# connectors.net
KiCad netlist of a schematic drawn in Altium Designer
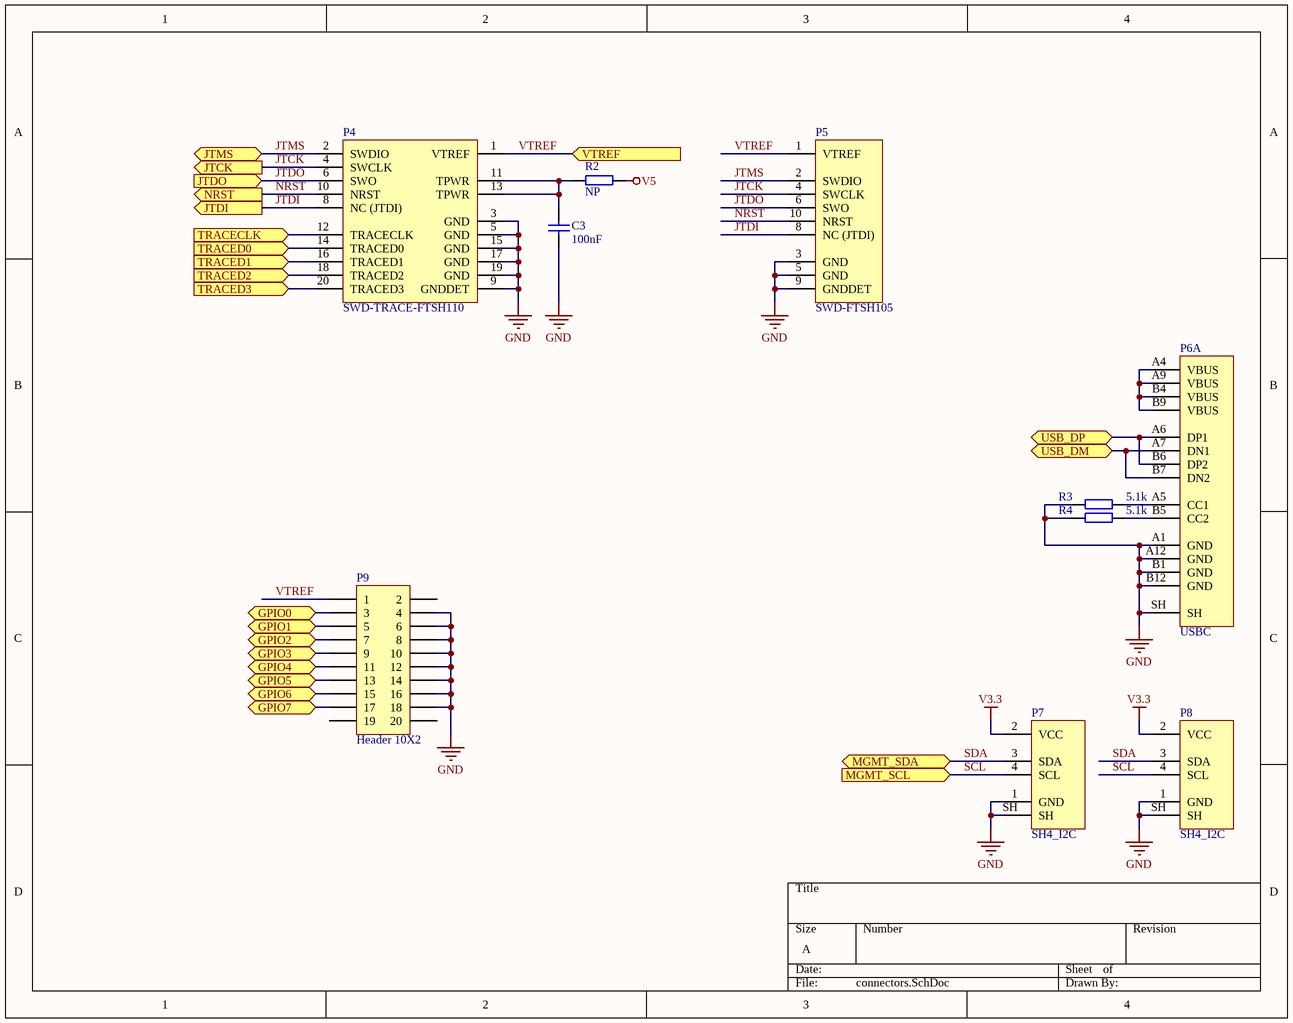
[diagram p0: connectors.SchDoc]

(export (version "E")
  (design (tool "Eeschema 10.0.6"))
  (components
    (comp (ref "C3") (value "100nF") (footprint "0402") (libsource (lib "misc") (part "Capacitor")))
    (comp (ref "P4")
      (value "SWD-TRACE-FTSH110")
      (footprint "FTSH110")
      (libsource (lib "misc") (part "SWD-TRACE-FTSH110"))
    )
    (comp (ref "P5")
      (value "SWD-FTSH105")
      (footprint "FTSH105")
      (libsource (lib "misc") (part "SWD-FTSH105"))
    )
    (comp (ref "P6") (value "USBC") (footprint "U262-161N-4BVC11") (libsource (lib "misc") (part "USBC")))
    (comp (ref "P7")
      (value "SH4_I2C")
      (footprint "SM04B")
      (description "Qwiic / STEMMA QT Compatible")
      (libsource (lib "misc") (part "SH4_I2C"))
    )
    (comp (ref "P8")
      (value "SH4_I2C")
      (footprint "SM04B")
      (description "Qwiic / STEMMA QT Compatible")
      (libsource (lib "misc") (part "SH4_I2C"))
    )
    (comp (ref "P9")
      (value "Header 10X2")
      (footprint "HDR2X10")
      (description "Header, 10-Pin, Dual row")
      (fields (field (name "PUBLISHER") "Altium Limited"))
      (libsource (lib "Miscellaneous Connectors") (part "Header 10X2"))
    )
    (comp (ref "R2") (value "NP") (footprint "0402") (libsource (lib "misc") (part "Resistor")))
    (comp (ref "R3") (value "5.1k") (footprint "0402") (libsource (lib "misc") (part "Resistor")))
    (comp (ref "R4") (value "5.1k") (footprint "0402") (libsource (lib "misc") (part "Resistor")))
  )
  (nets
    (net (code "1") (name "/GPIO0") (class "Default")
      (node (ref "P9") (pin "3") (pinfunction "3_3") (pintype "passive"))
    )
    (net (code "2") (name "/GPIO1") (class "Default")
      (node (ref "P9") (pin "5") (pinfunction "5_5") (pintype "passive"))
    )
    (net (code "3") (name "/GPIO2") (class "Default")
      (node (ref "P9") (pin "7") (pinfunction "7_7") (pintype "passive"))
    )
    (net (code "4") (name "/GPIO3") (class "Default")
      (node (ref "P9") (pin "9") (pinfunction "9_9") (pintype "passive"))
    )
    (net (code "5") (name "/GPIO4") (class "Default")
      (node (ref "P9") (pin "11") (pinfunction "11_11") (pintype "passive"))
    )
    (net (code "6") (name "/GPIO5") (class "Default")
      (node (ref "P9") (pin "13") (pinfunction "13_13") (pintype "passive"))
    )
    (net (code "7") (name "/GPIO6") (class "Default")
      (node (ref "P9") (pin "15") (pinfunction "15_15") (pintype "passive"))
    )
    (net (code "8") (name "/GPIO7") (class "Default")
      (node (ref "P9") (pin "17") (pinfunction "17_17") (pintype "passive"))
    )
    (net (code "9") (name "/JTCK") (class "Default")
      (node (ref "P4") (pin "4") (pinfunction "SWCLK_4") (pintype "passive"))
      (node (ref "P5") (pin "4") (pinfunction "SWCLK_4") (pintype "passive"))
    )
    (net (code "10") (name "/JTDI") (class "Default")
      (node (ref "P4") (pin "8") (pinfunction "NC_(JTDI)_8") (pintype "passive"))
      (node (ref "P5") (pin "8") (pinfunction "NC_(JTDI)_8") (pintype "passive"))
    )
    (net (code "11") (name "/JTDO") (class "Default")
      (node (ref "P4") (pin "6") (pinfunction "SWO_6") (pintype "passive"))
      (node (ref "P5") (pin "6") (pinfunction "SWO_6") (pintype "passive"))
    )
    (net (code "12") (name "/JTMS") (class "Default")
      (node (ref "P4") (pin "2") (pinfunction "SWDIO_2") (pintype "passive"))
      (node (ref "P5") (pin "2") (pinfunction "SWDIO_2") (pintype "passive"))
    )
    (net (code "13") (name "/NRST") (class "Default")
      (node (ref "P4") (pin "10") (pinfunction "NRST_10") (pintype "passive"))
      (node (ref "P5") (pin "10") (pinfunction "NRST_10") (pintype "passive"))
    )
    (net (code "14") (name "/SCL") (class "Default")
      (node (ref "P7") (pin "4") (pinfunction "SCL_4") (pintype "passive"))
      (node (ref "P8") (pin "4") (pinfunction "SCL_4") (pintype "passive"))
    )
    (net (code "15") (name "/SDA") (class "Default")
      (node (ref "P7") (pin "3") (pinfunction "SDA_3") (pintype "passive"))
      (node (ref "P8") (pin "3") (pinfunction "SDA_3") (pintype "passive"))
    )
    (net (code "16") (name "/TRACECLK") (class "Default")
      (node (ref "P4") (pin "12") (pinfunction "TRACECLK_12") (pintype "passive"))
    )
    (net (code "17") (name "/TRACED0") (class "Default")
      (node (ref "P4") (pin "14") (pinfunction "TRACED0_14") (pintype "passive"))
    )
    (net (code "18") (name "/TRACED1") (class "Default")
      (node (ref "P4") (pin "16") (pinfunction "TRACED1_16") (pintype "passive"))
    )
    (net (code "19") (name "/TRACED2") (class "Default")
      (node (ref "P4") (pin "18") (pinfunction "TRACED2_18") (pintype "passive"))
    )
    (net (code "20") (name "/TRACED3") (class "Default")
      (node (ref "P4") (pin "20") (pinfunction "TRACED3_20") (pintype "passive"))
    )
    (net (code "21") (name "/USB_DM") (class "Default")
      (node (ref "P6") (pin "A7") (pinfunction "DN1_A7") (pintype "passive"))
      (node (ref "P6") (pin "B7") (pinfunction "DN2_B7") (pintype "passive"))
    )
    (net (code "22") (name "/USB_DP") (class "Default")
      (node (ref "P6") (pin "A6") (pinfunction "DP1_A6") (pintype "passive"))
      (node (ref "P6") (pin "B6") (pinfunction "DP2_B6") (pintype "passive"))
    )
    (net (code "23") (name "/VTREF") (class "Default")
      (node (ref "P4") (pin "1") (pinfunction "VTREF_1") (pintype "passive"))
      (node (ref "P5") (pin "1") (pinfunction "VTREF_1") (pintype "passive"))
      (node (ref "P9") (pin "1") (pinfunction "1_1") (pintype "passive"))
    )
    (net (code "24") (name "GND") (class "Default")
      (node (ref "C3") (pin "1") (pinfunction "1_1") (pintype "passive"))
      (node (ref "P4") (pin "15") (pinfunction "GND_15") (pintype "passive"))
      (node (ref "P4") (pin "17") (pinfunction "GND_17") (pintype "passive"))
      (node (ref "P4") (pin "19") (pinfunction "GND_19") (pintype "passive"))
      (node (ref "P4") (pin "3") (pinfunction "GND_3") (pintype "passive"))
      (node (ref "P4") (pin "5") (pinfunction "GND_5") (pintype "passive"))
      (node (ref "P4") (pin "9") (pinfunction "GNDDET_9") (pintype "passive"))
      (node (ref "P5") (pin "3") (pinfunction "GND_3") (pintype "passive"))
      (node (ref "P5") (pin "5") (pinfunction "GND_5") (pintype "passive"))
      (node (ref "P5") (pin "9") (pinfunction "GNDDET_9") (pintype "passive"))
      (node (ref "P6") (pin "A1") (pinfunction "GND_A1") (pintype "passive"))
      (node (ref "P6") (pin "A12") (pinfunction "GND_A12") (pintype "passive"))
      (node (ref "P6") (pin "B1") (pinfunction "GND_B1") (pintype "passive"))
      (node (ref "P6") (pin "B12") (pinfunction "GND_B12") (pintype "passive"))
      (node (ref "P6") (pin "SH") (pinfunction "SH_SH") (pintype "passive"))
      (node (ref "P7") (pin "1") (pinfunction "GND_1") (pintype "passive"))
      (node (ref "P7") (pin "SH") (pinfunction "SH_SH") (pintype "passive"))
      (node (ref "P8") (pin "1") (pinfunction "GND_1") (pintype "passive"))
      (node (ref "P8") (pin "SH") (pinfunction "SH_SH") (pintype "passive"))
      (node (ref "P9") (pin "10") (pinfunction "10_10") (pintype "passive"))
      (node (ref "P9") (pin "12") (pinfunction "12_12") (pintype "passive"))
      (node (ref "P9") (pin "14") (pinfunction "14_14") (pintype "passive"))
      (node (ref "P9") (pin "16") (pinfunction "16_16") (pintype "passive"))
      (node (ref "P9") (pin "18") (pinfunction "18_18") (pintype "passive"))
      (node (ref "P9") (pin "4") (pinfunction "4_4") (pintype "passive"))
      (node (ref "P9") (pin "6") (pinfunction "6_6") (pintype "passive"))
      (node (ref "P9") (pin "8") (pinfunction "8_8") (pintype "passive"))
      (node (ref "R3") (pin "1") (pinfunction "1_1") (pintype "passive"))
      (node (ref "R4") (pin "1") (pinfunction "1_1") (pintype "passive"))
    )
    (net (code "25") (name "Net-(C3-Pad2)") (class "Default")
      (node (ref "C3") (pin "2") (pinfunction "2_2") (pintype "passive"))
      (node (ref "P4") (pin "11") (pinfunction "TPWR_11") (pintype "passive"))
      (node (ref "P4") (pin "13") (pinfunction "TPWR_13") (pintype "passive"))
      (node (ref "R2") (pin "1") (pinfunction "1_1") (pintype "passive"))
    )
    (net (code "26") (name "Net-(P6A-CC1)") (class "Default")
      (node (ref "P6") (pin "A5") (pinfunction "CC1_A5") (pintype "passive"))
      (node (ref "R3") (pin "2") (pinfunction "2_2") (pintype "passive"))
    )
    (net (code "27") (name "Net-(P6A-CC2)") (class "Default")
      (node (ref "P6") (pin "B5") (pinfunction "CC2_B5") (pintype "passive"))
      (node (ref "R4") (pin "2") (pinfunction "2_2") (pintype "passive"))
    )
    (net (code "28") (name "Net-(P6A-VBUS-PadA4)") (class "Default")
      (node (ref "P6") (pin "A4") (pinfunction "VBUS_A4") (pintype "passive"))
      (node (ref "P6") (pin "A9") (pinfunction "VBUS_A9") (pintype "passive"))
      (node (ref "P6") (pin "B4") (pinfunction "VBUS_B4") (pintype "passive"))
      (node (ref "P6") (pin "B9") (pinfunction "VBUS_B9") (pintype "passive"))
    )
    (net (code "29") (name "V3.3") (class "Default")
      (node (ref "P7") (pin "2") (pinfunction "VCC_2") (pintype "passive"))
      (node (ref "P8") (pin "2") (pinfunction "VCC_2") (pintype "passive"))
    )
    (net (code "30") (name "V5") (class "Default")
      (node (ref "R2") (pin "2") (pinfunction "2_2") (pintype "passive"))
    )
    (net (code "31") (name "unconnected-(P9-Pad2)") (class "Default")
      (node (ref "P9") (pin "2") (pinfunction "2_2") (pintype "passive"))
    )
    (net (code "32") (name "unconnected-(P9-Pad19)") (class "Default")
      (node (ref "P9") (pin "19") (pinfunction "19_19") (pintype "passive"))
    )
    (net (code "33") (name "unconnected-(P9-Pad20)") (class "Default")
      (node (ref "P9") (pin "20") (pinfunction "20_20") (pintype "passive"))
    )
  )
)
